# Pro_Trinket_Keyboard_V4_2.net
KiCad netlist of a schematic drawn in EAGLE
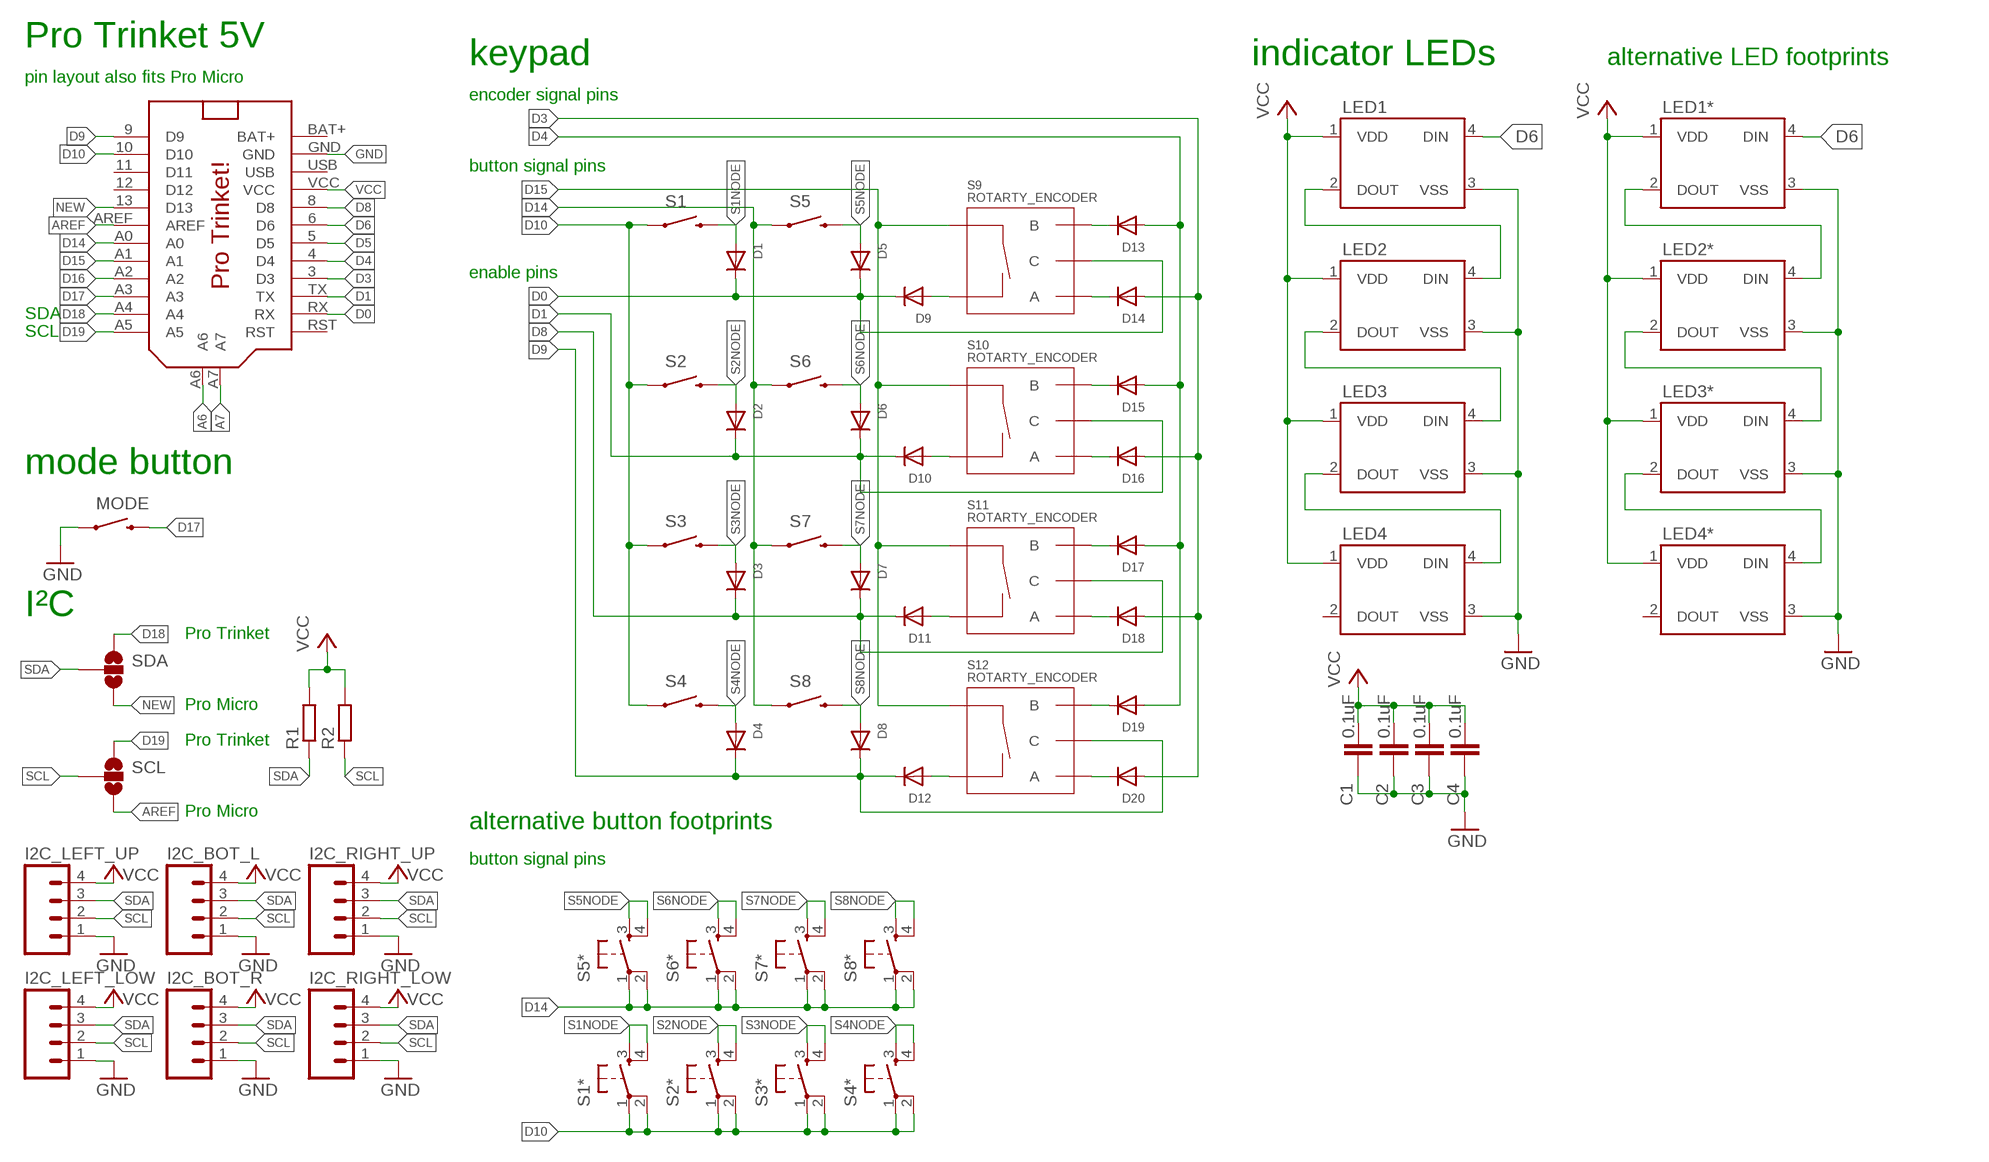
[diagram p0: schematic, sheet 1]

(export (version "E")
  (design (tool "Eeschema 10.0.6"))
  (components
    (comp (ref "C1")
      (value "0.1uF")
      (footprint "eagle-import:0603-CAP")
      (libsource (lib "eagle-import") (part "22PF-50V-5%(0603)"))
    )
    (comp (ref "C2")
      (value "0.1uF")
      (footprint "eagle-import:0603-CAP")
      (libsource (lib "eagle-import") (part "22PF-50V-5%(0603)"))
    )
    (comp (ref "C3")
      (value "0.1uF")
      (footprint "eagle-import:0603-CAP")
      (libsource (lib "eagle-import") (part "22PF-50V-5%(0603)"))
    )
    (comp (ref "C4")
      (value "0.1uF")
      (footprint "eagle-import:0603-CAP")
      (libsource (lib "eagle-import") (part "22PF-50V-5%(0603)"))
    )
    (comp (ref "D1")
      (value "DIODESOD-123")
      (footprint "eagle-import:SOD-123")
      (libsource (lib "eagle-import") (part "DIODESOD-123"))
    )
    (comp (ref "D2")
      (value "DIODESOD-123")
      (footprint "eagle-import:SOD-123")
      (libsource (lib "eagle-import") (part "DIODESOD-123"))
    )
    (comp (ref "D3")
      (value "DIODESOD-123")
      (footprint "eagle-import:SOD-123")
      (libsource (lib "eagle-import") (part "DIODESOD-123"))
    )
    (comp (ref "D4")
      (value "DIODESOD-123")
      (footprint "eagle-import:SOD-123")
      (libsource (lib "eagle-import") (part "DIODESOD-123"))
    )
    (comp (ref "D5")
      (value "DIODESOD-123")
      (footprint "eagle-import:SOD-123")
      (libsource (lib "eagle-import") (part "DIODESOD-123"))
    )
    (comp (ref "D6")
      (value "DIODESOD-123")
      (footprint "eagle-import:SOD-123")
      (libsource (lib "eagle-import") (part "DIODESOD-123"))
    )
    (comp (ref "D7")
      (value "DIODESOD-123")
      (footprint "eagle-import:SOD-123")
      (libsource (lib "eagle-import") (part "DIODESOD-123"))
    )
    (comp (ref "D8")
      (value "DIODESOD-123")
      (footprint "eagle-import:SOD-123")
      (libsource (lib "eagle-import") (part "DIODESOD-123"))
    )
    (comp (ref "D9")
      (value "DIODESOD-123")
      (footprint "eagle-import:SOD-123")
      (libsource (lib "eagle-import") (part "DIODESOD-123"))
    )
    (comp (ref "D10")
      (value "DIODESOD-123")
      (footprint "eagle-import:SOD-123")
      (libsource (lib "eagle-import") (part "DIODESOD-123"))
    )
    (comp (ref "D11")
      (value "DIODESOD-123")
      (footprint "eagle-import:SOD-123")
      (libsource (lib "eagle-import") (part "DIODESOD-123"))
    )
    (comp (ref "D12")
      (value "DIODESOD-123")
      (footprint "eagle-import:SOD-123")
      (libsource (lib "eagle-import") (part "DIODESOD-123"))
    )
    (comp (ref "D13")
      (value "DIODESOD-123")
      (footprint "eagle-import:SOD-123")
      (libsource (lib "eagle-import") (part "DIODESOD-123"))
    )
    (comp (ref "D14")
      (value "DIODESOD-123")
      (footprint "eagle-import:SOD-123")
      (libsource (lib "eagle-import") (part "DIODESOD-123"))
    )
    (comp (ref "D15")
      (value "DIODESOD-123")
      (footprint "eagle-import:SOD-123")
      (libsource (lib "eagle-import") (part "DIODESOD-123"))
    )
    (comp (ref "D16")
      (value "DIODESOD-123")
      (footprint "eagle-import:SOD-123")
      (libsource (lib "eagle-import") (part "DIODESOD-123"))
    )
    (comp (ref "D17")
      (value "DIODESOD-123")
      (footprint "eagle-import:SOD-123")
      (libsource (lib "eagle-import") (part "DIODESOD-123"))
    )
    (comp (ref "D18")
      (value "DIODESOD-123")
      (footprint "eagle-import:SOD-123")
      (libsource (lib "eagle-import") (part "DIODESOD-123"))
    )
    (comp (ref "D19")
      (value "DIODESOD-123")
      (footprint "eagle-import:SOD-123")
      (libsource (lib "eagle-import") (part "DIODESOD-123"))
    )
    (comp (ref "D20")
      (value "DIODESOD-123")
      (footprint "eagle-import:SOD-123")
      (libsource (lib "eagle-import") (part "DIODESOD-123"))
    )
    (comp (ref "I2C_BOT_L")
      (value "M04PTH")
      (footprint "eagle-import:1X04")
      (libsource (lib "eagle-import") (part "M04PTH"))
    )
    (comp (ref "I2C_BOT_R")
      (value "M04PTH")
      (footprint "eagle-import:1X04")
      (libsource (lib "eagle-import") (part "M04PTH"))
    )
    (comp (ref "I2C_LEFT_LOW")
      (value "M04PTH")
      (footprint "eagle-import:1X04")
      (libsource (lib "eagle-import") (part "M04PTH"))
    )
    (comp (ref "I2C_LEFT_UP")
      (value "M04PTH")
      (footprint "eagle-import:1X04")
      (libsource (lib "eagle-import") (part "M04PTH"))
    )
    (comp (ref "I2C_RIGHT_LOW")
      (value "M04PTH")
      (footprint "eagle-import:1X04")
      (libsource (lib "eagle-import") (part "M04PTH"))
    )
    (comp (ref "I2C_RIGHT_UP")
      (value "M04PTH")
      (footprint "eagle-import:1X04")
      (libsource (lib "eagle-import") (part "M04PTH"))
    )
    (comp (ref "LED1")
      (value "WS2812B")
      (footprint "eagle-import:WS2812B")
      (libsource (lib "eagle-import") (part "WS2812B"))
    )
    (comp (ref "LED1*")
      (value "WS2812B")
      (footprint "eagle-import:WS2812B")
      (libsource (lib "eagle-import") (part "WS2812B"))
    )
    (comp (ref "LED2")
      (value "WS2812B")
      (footprint "eagle-import:WS2812B")
      (libsource (lib "eagle-import") (part "WS2812B"))
    )
    (comp (ref "LED2*")
      (value "WS2812B")
      (footprint "eagle-import:WS2812B")
      (libsource (lib "eagle-import") (part "WS2812B"))
    )
    (comp (ref "LED3")
      (value "WS2812B")
      (footprint "eagle-import:WS2812B")
      (libsource (lib "eagle-import") (part "WS2812B"))
    )
    (comp (ref "LED3*")
      (value "WS2812B")
      (footprint "eagle-import:WS2812B")
      (libsource (lib "eagle-import") (part "WS2812B"))
    )
    (comp (ref "LED4")
      (value "WS2812B")
      (footprint "eagle-import:WS2812B")
      (libsource (lib "eagle-import") (part "WS2812B"))
    )
    (comp (ref "LED4*")
      (value "WS2812B")
      (footprint "eagle-import:WS2812B")
      (libsource (lib "eagle-import") (part "WS2812B"))
    )
    (comp (ref "MODE")
      (value "SWITCH-MOMENTARY-2SIDE_EZ")
      (footprint "eagle-import:TACTILE-PTH-SIDEEZ")
      (libsource (lib "eagle-import") (part "SWITCH-MOMENTARY-2SIDE_EZ"))
    )
    (comp (ref "PRO_TRINKET")
      (value "PRO_TRINKET")
      (footprint "eagle-import:PROTRINKET")
      (libsource (lib "eagle-import") (part "PRO_TRINKET"))
    )
    (comp (ref "R1")
      (value "RESISTORR805-0805")
      (footprint "eagle-import:R805")
      (libsource (lib "eagle-import") (part "RESISTOR-0805R805"))
    )
    (comp (ref "R2")
      (value "RESISTORR805-0805")
      (footprint "eagle-import:R805")
      (libsource (lib "eagle-import") (part "RESISTOR-0805R805"))
    )
    (comp (ref "S1")
      (value "SWITCH-MOMENTARY-212MM")
      (footprint "eagle-import:TACTILE-PTH-12MM")
      (libsource (lib "eagle-import") (part "SWITCH-MOMENTARY-212MM"))
    )
    (comp (ref "S1*")
      (value "TACTILE-SWITCH-PTH")
      (footprint "eagle-import:TAC-SWITCH-PTH")
      (libsource (lib "eagle-import") (part "TACTILE-SWITCH-PTH"))
    )
    (comp (ref "S2")
      (value "SWITCH-MOMENTARY-212MM")
      (footprint "eagle-import:TACTILE-PTH-12MM")
      (libsource (lib "eagle-import") (part "SWITCH-MOMENTARY-212MM"))
    )
    (comp (ref "S2*")
      (value "TACTILE-SWITCH-PTH")
      (footprint "eagle-import:TAC-SWITCH-PTH")
      (libsource (lib "eagle-import") (part "TACTILE-SWITCH-PTH"))
    )
    (comp (ref "S3")
      (value "SWITCH-MOMENTARY-212MM")
      (footprint "eagle-import:TACTILE-PTH-12MM")
      (libsource (lib "eagle-import") (part "SWITCH-MOMENTARY-212MM"))
    )
    (comp (ref "S3*")
      (value "TACTILE-SWITCH-PTH")
      (footprint "eagle-import:TAC-SWITCH-PTH")
      (libsource (lib "eagle-import") (part "TACTILE-SWITCH-PTH"))
    )
    (comp (ref "S4")
      (value "SWITCH-MOMENTARY-212MM")
      (footprint "eagle-import:TACTILE-PTH-12MM")
      (libsource (lib "eagle-import") (part "SWITCH-MOMENTARY-212MM"))
    )
    (comp (ref "S4*")
      (value "TACTILE-SWITCH-PTH")
      (footprint "eagle-import:TAC-SWITCH-PTH")
      (libsource (lib "eagle-import") (part "TACTILE-SWITCH-PTH"))
    )
    (comp (ref "S5")
      (value "SWITCH-MOMENTARY-212MM")
      (footprint "eagle-import:TACTILE-PTH-12MM")
      (libsource (lib "eagle-import") (part "SWITCH-MOMENTARY-212MM"))
    )
    (comp (ref "S5*")
      (value "TACTILE-SWITCH-PTH")
      (footprint "eagle-import:TAC-SWITCH-PTH")
      (libsource (lib "eagle-import") (part "TACTILE-SWITCH-PTH"))
    )
    (comp (ref "S6")
      (value "SWITCH-MOMENTARY-212MM")
      (footprint "eagle-import:TACTILE-PTH-12MM")
      (libsource (lib "eagle-import") (part "SWITCH-MOMENTARY-212MM"))
    )
    (comp (ref "S6*")
      (value "TACTILE-SWITCH-PTH")
      (footprint "eagle-import:TAC-SWITCH-PTH")
      (libsource (lib "eagle-import") (part "TACTILE-SWITCH-PTH"))
    )
    (comp (ref "S7")
      (value "SWITCH-MOMENTARY-212MM")
      (footprint "eagle-import:TACTILE-PTH-12MM")
      (libsource (lib "eagle-import") (part "SWITCH-MOMENTARY-212MM"))
    )
    (comp (ref "S7*")
      (value "TACTILE-SWITCH-PTH")
      (footprint "eagle-import:TAC-SWITCH-PTH")
      (libsource (lib "eagle-import") (part "TACTILE-SWITCH-PTH"))
    )
    (comp (ref "S8")
      (value "SWITCH-MOMENTARY-212MM")
      (footprint "eagle-import:TACTILE-PTH-12MM")
      (libsource (lib "eagle-import") (part "SWITCH-MOMENTARY-212MM"))
    )
    (comp (ref "S8*")
      (value "TACTILE-SWITCH-PTH")
      (footprint "eagle-import:TAC-SWITCH-PTH")
      (libsource (lib "eagle-import") (part "TACTILE-SWITCH-PTH"))
    )
    (comp (ref "S9")
      (value "ROTARTY_ENCODER")
      (footprint "eagle-import:ROTARY_ENC_PLAIN")
      (libsource (lib "eagle-import") (part "ROTARTY_ENCODER"))
    )
    (comp (ref "S10")
      (value "ROTARTY_ENCODER")
      (footprint "eagle-import:ROTARY_ENC_PLAIN")
      (libsource (lib "eagle-import") (part "ROTARTY_ENCODER"))
    )
    (comp (ref "S11")
      (value "ROTARTY_ENCODER")
      (footprint "eagle-import:ROTARY_ENC_PLAIN")
      (libsource (lib "eagle-import") (part "ROTARTY_ENCODER"))
    )
    (comp (ref "S12")
      (value "ROTARTY_ENCODER")
      (footprint "eagle-import:ROTARY_ENC_PLAIN")
      (libsource (lib "eagle-import") (part "ROTARTY_ENCODER"))
    )
    (comp (ref "SCL")
      (value "SOLDERJUMPER_2WAYS")
      (footprint "eagle-import:SJ_3")
      (libsource (lib "eagle-import") (part "SOLDERJUMPER_2WAYS"))
    )
    (comp (ref "SDA")
      (value "SOLDERJUMPER_2WAYS")
      (footprint "eagle-import:SJ_3")
      (libsource (lib "eagle-import") (part "SOLDERJUMPER_2WAYS"))
    )
  )
  (nets
    (net (code "1") (name "/BAT+") (class "Default")
      (node (ref "PRO_TRINKET") (pin "BAT+") (pinfunction "BAT+_BAT+") (pintype "power_in"))
    )
    (net (code "2") (name "/L1NODE") (class "Default")
      (node (ref "LED1") (pin "2") (pinfunction "DOUT_2") (pintype "output"))
      (node (ref "LED1*") (pin "2") (pinfunction "DOUT_2") (pintype "output"))
      (node (ref "LED2") (pin "4") (pinfunction "DIN_4") (pintype "input"))
      (node (ref "LED2*") (pin "4") (pinfunction "DIN_4") (pintype "input"))
    )
    (net (code "3") (name "/L2NODE") (class "Default")
      (node (ref "LED2") (pin "2") (pinfunction "DOUT_2") (pintype "output"))
      (node (ref "LED2*") (pin "2") (pinfunction "DOUT_2") (pintype "output"))
      (node (ref "LED3") (pin "4") (pinfunction "DIN_4") (pintype "input"))
      (node (ref "LED3*") (pin "4") (pinfunction "DIN_4") (pintype "input"))
    )
    (net (code "4") (name "/L3NODE") (class "Default")
      (node (ref "LED3") (pin "2") (pinfunction "DOUT_2") (pintype "output"))
      (node (ref "LED3*") (pin "2") (pinfunction "DOUT_2") (pintype "output"))
      (node (ref "LED4") (pin "4") (pinfunction "DIN_4") (pintype "input"))
      (node (ref "LED4*") (pin "4") (pinfunction "DIN_4") (pintype "input"))
    )
    (net (code "5") (name "/USB") (class "Default")
      (node (ref "PRO_TRINKET") (pin "USB") (pinfunction "USB_USB") (pintype "power_in"))
    )
    (net (code "6") (name "A6") (class "Default")
      (node (ref "PRO_TRINKET") (pin "A6") (pinfunction "A6_A6") (pintype "passive"))
    )
    (net (code "7") (name "A7") (class "Default")
      (node (ref "PRO_TRINKET") (pin "A7") (pinfunction "A7_A7") (pintype "passive"))
    )
    (net (code "8") (name "AREF") (class "Default")
      (node (ref "PRO_TRINKET") (pin "AREF") (pinfunction "AREF_AREF") (pintype "passive"))
      (node (ref "SCL") (pin "3") (pinfunction "3_3") (pintype "passive"))
    )
    (net (code "9") (name "D0") (class "Default")
      (node (ref "D1") (pin "C") (pinfunction "C_C") (pintype "passive"))
      (node (ref "D5") (pin "C") (pinfunction "C_C") (pintype "passive"))
      (node (ref "D9") (pin "C") (pinfunction "C_C") (pintype "passive"))
      (node (ref "PRO_TRINKET") (pin "RX") (pinfunction "RX_RX") (pintype "bidirectional"))
      (node (ref "S9") (pin "C") (pinfunction "C_C") (pintype "bidirectional"))
    )
    (net (code "10") (name "D1") (class "Default")
      (node (ref "D10") (pin "C") (pinfunction "C_C") (pintype "passive"))
      (node (ref "D2") (pin "C") (pinfunction "C_C") (pintype "passive"))
      (node (ref "D6") (pin "C") (pinfunction "C_C") (pintype "passive"))
      (node (ref "PRO_TRINKET") (pin "TX") (pinfunction "TX_TX") (pintype "bidirectional"))
      (node (ref "S10") (pin "C") (pinfunction "C_C") (pintype "bidirectional"))
    )
    (net (code "11") (name "D3") (class "Default")
      (node (ref "D14") (pin "A") (pinfunction "A_A") (pintype "passive"))
      (node (ref "D16") (pin "A") (pinfunction "A_A") (pintype "passive"))
      (node (ref "D18") (pin "A") (pinfunction "A_A") (pintype "passive"))
      (node (ref "D20") (pin "A") (pinfunction "A_A") (pintype "passive"))
      (node (ref "PRO_TRINKET") (pin "3") (pinfunction "D3_3") (pintype "bidirectional"))
    )
    (net (code "12") (name "D4") (class "Default")
      (node (ref "D13") (pin "A") (pinfunction "A_A") (pintype "passive"))
      (node (ref "D15") (pin "A") (pinfunction "A_A") (pintype "passive"))
      (node (ref "D17") (pin "A") (pinfunction "A_A") (pintype "passive"))
      (node (ref "D19") (pin "A") (pinfunction "A_A") (pintype "passive"))
      (node (ref "PRO_TRINKET") (pin "4") (pinfunction "D4_4") (pintype "bidirectional"))
    )
    (net (code "13") (name "D5") (class "Default")
      (node (ref "PRO_TRINKET") (pin "5") (pinfunction "D5_5") (pintype "bidirectional"))
    )
    (net (code "14") (name "D6") (class "Default")
      (node (ref "LED1") (pin "4") (pinfunction "DIN_4") (pintype "input"))
      (node (ref "LED1*") (pin "4") (pinfunction "DIN_4") (pintype "input"))
      (node (ref "PRO_TRINKET") (pin "6") (pinfunction "D6_6") (pintype "bidirectional"))
    )
    (net (code "15") (name "D8") (class "Default")
      (node (ref "D11") (pin "C") (pinfunction "C_C") (pintype "passive"))
      (node (ref "D3") (pin "C") (pinfunction "C_C") (pintype "passive"))
      (node (ref "D7") (pin "C") (pinfunction "C_C") (pintype "passive"))
      (node (ref "PRO_TRINKET") (pin "8") (pinfunction "D8_8") (pintype "bidirectional"))
      (node (ref "S11") (pin "C") (pinfunction "C_C") (pintype "bidirectional"))
    )
    (net (code "16") (name "D9") (class "Default")
      (node (ref "D12") (pin "C") (pinfunction "C_C") (pintype "passive"))
      (node (ref "D4") (pin "C") (pinfunction "C_C") (pintype "passive"))
      (node (ref "D8") (pin "C") (pinfunction "C_C") (pintype "passive"))
      (node (ref "PRO_TRINKET") (pin "9") (pinfunction "D9_9") (pintype "bidirectional"))
      (node (ref "S12") (pin "C") (pinfunction "C_C") (pintype "bidirectional"))
    )
    (net (code "17") (name "D10") (class "Default")
      (node (ref "PRO_TRINKET") (pin "10") (pinfunction "D10_10") (pintype "bidirectional"))
      (node (ref "S1") (pin "1") (pinfunction "1_1") (pintype "passive"))
      (node (ref "S1") (pin "2") (pinfunction "1_2") (pintype "passive"))
      (node (ref "S1*") (pin "1") (pinfunction "1_1") (pintype "passive"))
      (node (ref "S1*") (pin "2") (pinfunction "2_2") (pintype "passive"))
      (node (ref "S2") (pin "1") (pinfunction "1_1") (pintype "passive"))
      (node (ref "S2") (pin "2") (pinfunction "1_2") (pintype "passive"))
      (node (ref "S2*") (pin "1") (pinfunction "1_1") (pintype "passive"))
      (node (ref "S2*") (pin "2") (pinfunction "2_2") (pintype "passive"))
      (node (ref "S3") (pin "1") (pinfunction "1_1") (pintype "passive"))
      (node (ref "S3") (pin "2") (pinfunction "1_2") (pintype "passive"))
      (node (ref "S3*") (pin "1") (pinfunction "1_1") (pintype "passive"))
      (node (ref "S3*") (pin "2") (pinfunction "2_2") (pintype "passive"))
      (node (ref "S4") (pin "1") (pinfunction "1_1") (pintype "passive"))
      (node (ref "S4") (pin "2") (pinfunction "1_2") (pintype "passive"))
      (node (ref "S4*") (pin "1") (pinfunction "1_1") (pintype "passive"))
      (node (ref "S4*") (pin "2") (pinfunction "2_2") (pintype "passive"))
    )
    (net (code "18") (name "D14") (class "Default")
      (node (ref "PRO_TRINKET") (pin "A0") (pinfunction "A0_A0") (pintype "bidirectional"))
      (node (ref "S5") (pin "1") (pinfunction "1_1") (pintype "passive"))
      (node (ref "S5") (pin "2") (pinfunction "1_2") (pintype "passive"))
      (node (ref "S5*") (pin "1") (pinfunction "1_1") (pintype "passive"))
      (node (ref "S5*") (pin "2") (pinfunction "2_2") (pintype "passive"))
      (node (ref "S6") (pin "1") (pinfunction "1_1") (pintype "passive"))
      (node (ref "S6") (pin "2") (pinfunction "1_2") (pintype "passive"))
      (node (ref "S6*") (pin "1") (pinfunction "1_1") (pintype "passive"))
      (node (ref "S6*") (pin "2") (pinfunction "2_2") (pintype "passive"))
      (node (ref "S7") (pin "1") (pinfunction "1_1") (pintype "passive"))
      (node (ref "S7") (pin "2") (pinfunction "1_2") (pintype "passive"))
      (node (ref "S7*") (pin "1") (pinfunction "1_1") (pintype "passive"))
      (node (ref "S7*") (pin "2") (pinfunction "2_2") (pintype "passive"))
      (node (ref "S8") (pin "1") (pinfunction "1_1") (pintype "passive"))
      (node (ref "S8") (pin "2") (pinfunction "1_2") (pintype "passive"))
      (node (ref "S8*") (pin "1") (pinfunction "1_1") (pintype "passive"))
      (node (ref "S8*") (pin "2") (pinfunction "2_2") (pintype "passive"))
    )
    (net (code "19") (name "D15") (class "Default")
      (node (ref "PRO_TRINKET") (pin "A1") (pinfunction "A1_A1") (pintype "bidirectional"))
      (node (ref "S10") (pin "SW+") (pinfunction "SW+_SW+") (pintype "bidirectional"))
      (node (ref "S11") (pin "SW+") (pinfunction "SW+_SW+") (pintype "bidirectional"))
      (node (ref "S12") (pin "SW+") (pinfunction "SW+_SW+") (pintype "bidirectional"))
      (node (ref "S9") (pin "SW+") (pinfunction "SW+_SW+") (pintype "bidirectional"))
    )
    (net (code "20") (name "D16") (class "Default")
      (node (ref "PRO_TRINKET") (pin "A2") (pinfunction "A2_A2") (pintype "bidirectional"))
    )
    (net (code "21") (name "D17") (class "Default")
      (node (ref "MODE") (pin "2") (pinfunction "2_2") (pintype "passive"))
      (node (ref "PRO_TRINKET") (pin "A3") (pinfunction "A3_A3") (pintype "bidirectional"))
    )
    (net (code "22") (name "D18") (class "Default")
      (node (ref "PRO_TRINKET") (pin "A4") (pinfunction "A4_A4") (pintype "bidirectional"))
      (node (ref "SDA") (pin "1") (pinfunction "1_1") (pintype "passive"))
    )
    (net (code "23") (name "D19") (class "Default")
      (node (ref "PRO_TRINKET") (pin "A5") (pinfunction "A5_A5") (pintype "bidirectional"))
      (node (ref "SCL") (pin "1") (pinfunction "1_1") (pintype "passive"))
    )
    (net (code "24") (name "GND") (class "Default")
      (node (ref "C1") (pin "1") (pinfunction "1_1") (pintype "passive"))
      (node (ref "C2") (pin "1") (pinfunction "1_1") (pintype "passive"))
      (node (ref "C3") (pin "1") (pinfunction "1_1") (pintype "passive"))
      (node (ref "C4") (pin "1") (pinfunction "1_1") (pintype "passive"))
      (node (ref "I2C_BOT_L") (pin "1") (pinfunction "1_1") (pintype "passive"))
      (node (ref "I2C_BOT_R") (pin "1") (pinfunction "1_1") (pintype "passive"))
      (node (ref "I2C_LEFT_LOW") (pin "1") (pinfunction "1_1") (pintype "passive"))
      (node (ref "I2C_LEFT_UP") (pin "1") (pinfunction "1_1") (pintype "passive"))
      (node (ref "I2C_RIGHT_LOW") (pin "1") (pinfunction "1_1") (pintype "passive"))
      (node (ref "I2C_RIGHT_UP") (pin "1") (pinfunction "1_1") (pintype "passive"))
      (node (ref "LED1") (pin "3") (pinfunction "VSS_3") (pintype "power_in"))
      (node (ref "LED1*") (pin "3") (pinfunction "VSS_3") (pintype "power_in"))
      (node (ref "LED2") (pin "3") (pinfunction "VSS_3") (pintype "power_in"))
      (node (ref "LED2*") (pin "3") (pinfunction "VSS_3") (pintype "power_in"))
      (node (ref "LED3") (pin "3") (pinfunction "VSS_3") (pintype "power_in"))
      (node (ref "LED3*") (pin "3") (pinfunction "VSS_3") (pintype "power_in"))
      (node (ref "LED4") (pin "3") (pinfunction "VSS_3") (pintype "power_in"))
      (node (ref "LED4*") (pin "3") (pinfunction "VSS_3") (pintype "power_in"))
      (node (ref "MODE") (pin "1") (pinfunction "1_1") (pintype "passive"))
      (node (ref "PRO_TRINKET") (pin "GND") (pinfunction "GND_GND") (pintype "power_in"))
    )
    (net (code "25") (name "NEW") (class "Default")
      (node (ref "PRO_TRINKET") (pin "13") (pinfunction "D13_13") (pintype "bidirectional"))
      (node (ref "SDA") (pin "3") (pinfunction "3_3") (pintype "passive"))
    )
    (net (code "26") (name "Net-(D9-PadA)") (class "Default")
      (node (ref "D9") (pin "A") (pinfunction "A_A") (pintype "passive"))
      (node (ref "S9") (pin "SW-") (pinfunction "SW-_SW-") (pintype "bidirectional"))
    )
    (net (code "27") (name "Net-(D10-PadA)") (class "Default")
      (node (ref "D10") (pin "A") (pinfunction "A_A") (pintype "passive"))
      (node (ref "S10") (pin "SW-") (pinfunction "SW-_SW-") (pintype "bidirectional"))
    )
    (net (code "28") (name "Net-(D11-PadA)") (class "Default")
      (node (ref "D11") (pin "A") (pinfunction "A_A") (pintype "passive"))
      (node (ref "S11") (pin "SW-") (pinfunction "SW-_SW-") (pintype "bidirectional"))
    )
    (net (code "29") (name "Net-(D12-PadA)") (class "Default")
      (node (ref "D12") (pin "A") (pinfunction "A_A") (pintype "passive"))
      (node (ref "S12") (pin "SW-") (pinfunction "SW-_SW-") (pintype "bidirectional"))
    )
    (net (code "30") (name "Net-(D13-PadC)") (class "Default")
      (node (ref "D13") (pin "C") (pinfunction "C_C") (pintype "passive"))
      (node (ref "S9") (pin "B") (pinfunction "B_B") (pintype "bidirectional"))
    )
    (net (code "31") (name "Net-(D14-PadC)") (class "Default")
      (node (ref "D14") (pin "C") (pinfunction "C_C") (pintype "passive"))
      (node (ref "S9") (pin "A") (pinfunction "A_A") (pintype "bidirectional"))
    )
    (net (code "32") (name "Net-(D15-PadC)") (class "Default")
      (node (ref "D15") (pin "C") (pinfunction "C_C") (pintype "passive"))
      (node (ref "S10") (pin "B") (pinfunction "B_B") (pintype "bidirectional"))
    )
    (net (code "33") (name "Net-(D16-PadC)") (class "Default")
      (node (ref "D16") (pin "C") (pinfunction "C_C") (pintype "passive"))
      (node (ref "S10") (pin "A") (pinfunction "A_A") (pintype "bidirectional"))
    )
    (net (code "34") (name "Net-(D17-PadC)") (class "Default")
      (node (ref "D17") (pin "C") (pinfunction "C_C") (pintype "passive"))
      (node (ref "S11") (pin "B") (pinfunction "B_B") (pintype "bidirectional"))
    )
    (net (code "35") (name "Net-(D18-PadC)") (class "Default")
      (node (ref "D18") (pin "C") (pinfunction "C_C") (pintype "passive"))
      (node (ref "S11") (pin "A") (pinfunction "A_A") (pintype "bidirectional"))
    )
    (net (code "36") (name "Net-(D19-PadC)") (class "Default")
      (node (ref "D19") (pin "C") (pinfunction "C_C") (pintype "passive"))
      (node (ref "S12") (pin "B") (pinfunction "B_B") (pintype "bidirectional"))
    )
    (net (code "37") (name "Net-(D20-PadC)") (class "Default")
      (node (ref "D20") (pin "C") (pinfunction "C_C") (pintype "passive"))
      (node (ref "S12") (pin "A") (pinfunction "A_A") (pintype "bidirectional"))
    )
    (net (code "38") (name "S1NODE") (class "Default")
      (node (ref "D1") (pin "A") (pinfunction "A_A") (pintype "passive"))
      (node (ref "S1") (pin "3") (pinfunction "2_3") (pintype "passive"))
      (node (ref "S1") (pin "4") (pinfunction "2_4") (pintype "passive"))
      (node (ref "S1*") (pin "3") (pinfunction "3_3") (pintype "passive"))
      (node (ref "S1*") (pin "4") (pinfunction "4_4") (pintype "passive"))
    )
    (net (code "39") (name "S2NODE") (class "Default")
      (node (ref "D2") (pin "A") (pinfunction "A_A") (pintype "passive"))
      (node (ref "S2") (pin "3") (pinfunction "2_3") (pintype "passive"))
      (node (ref "S2") (pin "4") (pinfunction "2_4") (pintype "passive"))
      (node (ref "S2*") (pin "3") (pinfunction "3_3") (pintype "passive"))
      (node (ref "S2*") (pin "4") (pinfunction "4_4") (pintype "passive"))
    )
    (net (code "40") (name "S3NODE") (class "Default")
      (node (ref "D3") (pin "A") (pinfunction "A_A") (pintype "passive"))
      (node (ref "S3") (pin "3") (pinfunction "2_3") (pintype "passive"))
      (node (ref "S3") (pin "4") (pinfunction "2_4") (pintype "passive"))
      (node (ref "S3*") (pin "3") (pinfunction "3_3") (pintype "passive"))
      (node (ref "S3*") (pin "4") (pinfunction "4_4") (pintype "passive"))
    )
    (net (code "41") (name "S4NODE") (class "Default")
      (node (ref "D4") (pin "A") (pinfunction "A_A") (pintype "passive"))
      (node (ref "S4") (pin "3") (pinfunction "2_3") (pintype "passive"))
      (node (ref "S4") (pin "4") (pinfunction "2_4") (pintype "passive"))
      (node (ref "S4*") (pin "3") (pinfunction "3_3") (pintype "passive"))
      (node (ref "S4*") (pin "4") (pinfunction "4_4") (pintype "passive"))
    )
    (net (code "42") (name "S5NODE") (class "Default")
      (node (ref "D5") (pin "A") (pinfunction "A_A") (pintype "passive"))
      (node (ref "S5") (pin "3") (pinfunction "2_3") (pintype "passive"))
      (node (ref "S5") (pin "4") (pinfunction "2_4") (pintype "passive"))
      (node (ref "S5*") (pin "3") (pinfunction "3_3") (pintype "passive"))
      (node (ref "S5*") (pin "4") (pinfunction "4_4") (pintype "passive"))
    )
    (net (code "43") (name "S6NODE") (class "Default")
      (node (ref "D6") (pin "A") (pinfunction "A_A") (pintype "passive"))
      (node (ref "S6") (pin "3") (pinfunction "2_3") (pintype "passive"))
      (node (ref "S6") (pin "4") (pinfunction "2_4") (pintype "passive"))
      (node (ref "S6*") (pin "3") (pinfunction "3_3") (pintype "passive"))
      (node (ref "S6*") (pin "4") (pinfunction "4_4") (pintype "passive"))
    )
    (net (code "44") (name "S7NODE") (class "Default")
      (node (ref "D7") (pin "A") (pinfunction "A_A") (pintype "passive"))
      (node (ref "S7") (pin "3") (pinfunction "2_3") (pintype "passive"))
      (node (ref "S7") (pin "4") (pinfunction "2_4") (pintype "passive"))
      (node (ref "S7*") (pin "3") (pinfunction "3_3") (pintype "passive"))
      (node (ref "S7*") (pin "4") (pinfunction "4_4") (pintype "passive"))
    )
    (net (code "45") (name "S8NODE") (class "Default")
      (node (ref "D8") (pin "A") (pinfunction "A_A") (pintype "passive"))
      (node (ref "S8") (pin "3") (pinfunction "2_3") (pintype "passive"))
      (node (ref "S8") (pin "4") (pinfunction "2_4") (pintype "passive"))
      (node (ref "S8*") (pin "3") (pinfunction "3_3") (pintype "passive"))
      (node (ref "S8*") (pin "4") (pinfunction "4_4") (pintype "passive"))
    )
    (net (code "46") (name "SCL") (class "Default")
      (node (ref "I2C_BOT_L") (pin "2") (pinfunction "2_2") (pintype "passive"))
      (node (ref "I2C_BOT_R") (pin "2") (pinfunction "2_2") (pintype "passive"))
      (node (ref "I2C_LEFT_LOW") (pin "2") (pinfunction "2_2") (pintype "passive"))
      (node (ref "I2C_LEFT_UP") (pin "2") (pinfunction "2_2") (pintype "passive"))
      (node (ref "I2C_RIGHT_LOW") (pin "2") (pinfunction "2_2") (pintype "passive"))
      (node (ref "I2C_RIGHT_UP") (pin "2") (pinfunction "2_2") (pintype "passive"))
      (node (ref "R2") (pin "1") (pinfunction "1_1") (pintype "passive"))
      (node (ref "SCL") (pin "2") (pinfunction "2_2") (pintype "passive"))
    )
    (net (code "47") (name "SDA") (class "Default")
      (node (ref "I2C_BOT_L") (pin "3") (pinfunction "3_3") (pintype "passive"))
      (node (ref "I2C_BOT_R") (pin "3") (pinfunction "3_3") (pintype "passive"))
      (node (ref "I2C_LEFT_LOW") (pin "3") (pinfunction "3_3") (pintype "passive"))
      (node (ref "I2C_LEFT_UP") (pin "3") (pinfunction "3_3") (pintype "passive"))
      (node (ref "I2C_RIGHT_LOW") (pin "3") (pinfunction "3_3") (pintype "passive"))
      (node (ref "I2C_RIGHT_UP") (pin "3") (pinfunction "3_3") (pintype "passive"))
      (node (ref "R1") (pin "1") (pinfunction "1_1") (pintype "passive"))
      (node (ref "SDA") (pin "2") (pinfunction "2_2") (pintype "passive"))
    )
    (net (code "48") (name "VCC") (class "Default")
      (node (ref "C1") (pin "2") (pinfunction "2_2") (pintype "passive"))
      (node (ref "C2") (pin "2") (pinfunction "2_2") (pintype "passive"))
      (node (ref "C3") (pin "2") (pinfunction "2_2") (pintype "passive"))
      (node (ref "C4") (pin "2") (pinfunction "2_2") (pintype "passive"))
      (node (ref "I2C_BOT_L") (pin "4") (pinfunction "4_4") (pintype "passive"))
      (node (ref "I2C_BOT_R") (pin "4") (pinfunction "4_4") (pintype "passive"))
      (node (ref "I2C_LEFT_LOW") (pin "4") (pinfunction "4_4") (pintype "passive"))
      (node (ref "I2C_LEFT_UP") (pin "4") (pinfunction "4_4") (pintype "passive"))
      (node (ref "I2C_RIGHT_LOW") (pin "4") (pinfunction "4_4") (pintype "passive"))
      (node (ref "I2C_RIGHT_UP") (pin "4") (pinfunction "4_4") (pintype "passive"))
      (node (ref "LED1") (pin "1") (pinfunction "VDD_1") (pintype "power_in"))
      (node (ref "LED1*") (pin "1") (pinfunction "VDD_1") (pintype "power_in"))
      (node (ref "LED2") (pin "1") (pinfunction "VDD_1") (pintype "power_in"))
      (node (ref "LED2*") (pin "1") (pinfunction "VDD_1") (pintype "power_in"))
      (node (ref "LED3") (pin "1") (pinfunction "VDD_1") (pintype "power_in"))
      (node (ref "LED3*") (pin "1") (pinfunction "VDD_1") (pintype "power_in"))
      (node (ref "LED4") (pin "1") (pinfunction "VDD_1") (pintype "power_in"))
      (node (ref "LED4*") (pin "1") (pinfunction "VDD_1") (pintype "power_in"))
      (node (ref "PRO_TRINKET") (pin "VCC") (pinfunction "VCC_VCC") (pintype "power_in"))
      (node (ref "R1") (pin "2") (pinfunction "2_2") (pintype "passive"))
      (node (ref "R2") (pin "2") (pinfunction "2_2") (pintype "passive"))
    )
    (net (code "49") (name "unconnected-(LED4*-DOUT-Pad2)") (class "Default")
      (node (ref "LED4*") (pin "2") (pinfunction "DOUT_2") (pintype "output"))
    )
    (net (code "50") (name "unconnected-(LED4-DOUT-Pad2)") (class "Default")
      (node (ref "LED4") (pin "2") (pinfunction "DOUT_2") (pintype "output"))
    )
    (net (code "51") (name "unconnected-(PRO_TRINKET-D11-Pad11)") (class "Default")
      (node (ref "PRO_TRINKET") (pin "11") (pinfunction "D11_11") (pintype "bidirectional"))
    )
    (net (code "52") (name "unconnected-(PRO_TRINKET-D12-Pad12)") (class "Default")
      (node (ref "PRO_TRINKET") (pin "12") (pinfunction "D12_12") (pintype "bidirectional"))
    )
    (net (code "53") (name "unconnected-(PRO_TRINKET-PadRST)") (class "Default")
      (node (ref "PRO_TRINKET") (pin "RST") (pinfunction "RST_RST") (pintype "passive"))
    )
  )
)
